# attiny85.net
KiCad netlist of a schematic drawn in EAGLE
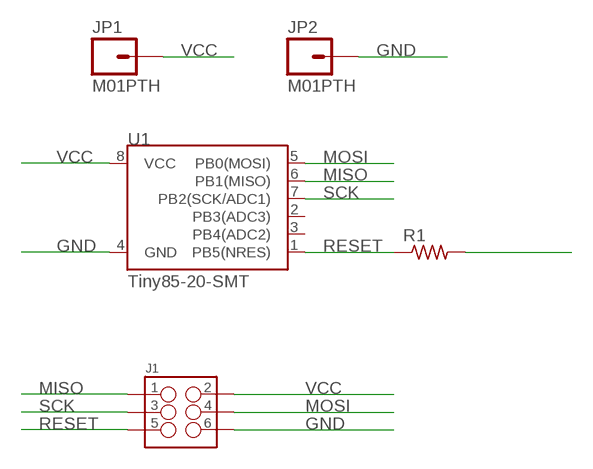
[diagram p0: schematic, sheet 1]

(export (version "E")
  (design (tool "Eeschema 10.0.6"))
  (components
    (comp (ref "J1")
      (value "M03X2SMT")
      (footprint "eagle-import:2X3_SMT_POSTS")
      (libsource (lib "eagle-import") (part "M03X2SMT"))
    )
    (comp (ref "JP1")
      (value "M01PTH")
      (footprint "eagle-import:1X01")
      (libsource (lib "eagle-import") (part "M01PTH"))
    )
    (comp (ref "JP2")
      (value "M01PTH")
      (footprint "eagle-import:1X01")
      (libsource (lib "eagle-import") (part "M01PTH"))
    )
    (comp (ref "R1")
      (value "R-US_M0805")
      (footprint "eagle-import:M0805")
      (libsource (lib "eagle-import") (part "R-US_M0805"))
    )
    (comp (ref "U1")
      (value "Tiny85-20-SMT")
      (footprint "eagle-import:SO08-EIAJ")
      (libsource (lib "eagle-import") (part "ATTINY45TINY85-20-SMT"))
    )
  )
  (nets
    (net (code "1") (name "/GND") (class "Default")
      (node (ref "J1") (pin "6") (pinfunction "6_6") (pintype "bidirectional"))
      (node (ref "JP2") (pin "1") (pinfunction "1_1") (pintype "passive"))
      (node (ref "U1") (pin "4") (pinfunction "GND_4") (pintype "bidirectional"))
    )
    (net (code "2") (name "/MISO") (class "Default")
      (node (ref "J1") (pin "1") (pinfunction "1_1") (pintype "bidirectional"))
      (node (ref "U1") (pin "6") (pinfunction "PB1(MISO)_6") (pintype "bidirectional"))
    )
    (net (code "3") (name "/MOSI") (class "Default")
      (node (ref "J1") (pin "4") (pinfunction "4_4") (pintype "bidirectional"))
      (node (ref "U1") (pin "5") (pinfunction "PB0(MOSI)_5") (pintype "bidirectional"))
    )
    (net (code "4") (name "/RESET") (class "Default")
      (node (ref "J1") (pin "5") (pinfunction "5_5") (pintype "bidirectional"))
      (node (ref "R1") (pin "1") (pinfunction "1_1") (pintype "passive"))
      (node (ref "U1") (pin "1") (pinfunction "PB5(NRES)_1") (pintype "bidirectional"))
    )
    (net (code "5") (name "/SCK") (class "Default")
      (node (ref "J1") (pin "3") (pinfunction "3_3") (pintype "bidirectional"))
      (node (ref "U1") (pin "7") (pinfunction "PB2(SCK/ADC1)_7") (pintype "bidirectional"))
    )
    (net (code "6") (name "/VCC") (class "Default")
      (node (ref "J1") (pin "2") (pinfunction "2_2") (pintype "bidirectional"))
      (node (ref "JP1") (pin "1") (pinfunction "1_1") (pintype "passive"))
      (node (ref "R1") (pin "2") (pinfunction "2_2") (pintype "passive"))
      (node (ref "U1") (pin "8") (pinfunction "VCC_8") (pintype "bidirectional"))
    )
    (net (code "7") (name "unconnected-(U1-PB3(ADC3)-Pad2)") (class "Default")
      (node (ref "U1") (pin "2") (pinfunction "PB3(ADC3)_2") (pintype "bidirectional"))
    )
    (net (code "8") (name "unconnected-(U1-PB4(ADC2)-Pad3)") (class "Default")
      (node (ref "U1") (pin "3") (pinfunction "PB4(ADC2)_3") (pintype "bidirectional"))
    )
  )
)
